# Back_EMF.net
KiCad netlist of a schematic drawn in Altium Designer
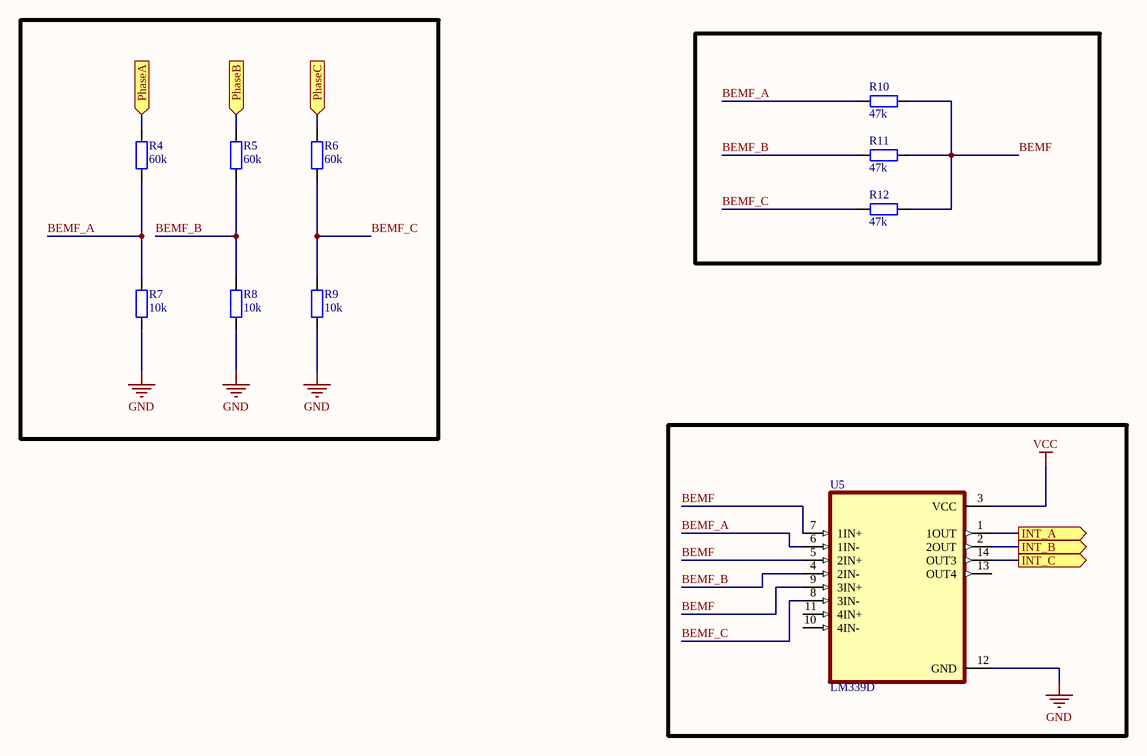
[diagram p0: Back_EMF.SchDoc]

(export (version "E")
  (design (tool "Eeschema 10.0.6"))
  (components
    (comp (ref "R4")
      (value "60k")
      (footprint "tro smd 0603")
      (description "Dán")
      (libsource (lib "Dien Tro") (part "Tro 0603 1% 10k"))
    )
    (comp (ref "R5")
      (value "60k")
      (footprint "tro smd 0603")
      (description "Dán")
      (libsource (lib "Dien Tro") (part "Tro 0603 1% 10k"))
    )
    (comp (ref "R6")
      (value "60k")
      (footprint "tro smd 0603")
      (description "Dán")
      (libsource (lib "Dien Tro") (part "Tro 0603 1% 10k"))
    )
    (comp (ref "R7")
      (value "10k")
      (footprint "tro smd 0603")
      (description "Dán")
      (libsource (lib "Dien Tro") (part "Tro 0603 1% 10k"))
    )
    (comp (ref "R8")
      (value "10k")
      (footprint "tro smd 0603")
      (description "Dán")
      (libsource (lib "Dien Tro") (part "Tro 0603 1% 10k"))
    )
    (comp (ref "R9")
      (value "10k")
      (footprint "tro smd 0603")
      (description "Dán")
      (libsource (lib "Dien Tro") (part "Tro 0603 1% 10k"))
    )
    (comp (ref "R10")
      (value "47k")
      (footprint "tro smd 0603")
      (description "Dán")
      (libsource (lib "Dien Tro") (part "Tro 0603 5% 47k"))
    )
    (comp (ref "R11")
      (value "47k")
      (footprint "tro smd 0603")
      (description "Dán")
      (libsource (lib "Dien Tro") (part "Tro 0603 5% 47k"))
    )
    (comp (ref "R12")
      (value "47k")
      (footprint "tro smd 0603")
      (description "Dán")
      (libsource (lib "Dien Tro") (part "Tro 0603 5% 47k"))
    )
    (comp (ref "U5")
      (value "LM339D")
      (footprint "SOIC127P600X175-14N")
      (libsource (lib "LM339D") (part "LM339D"))
    )
  )
  (nets
    (net (code "1") (name "/BEMF") (class "Default")
      (node (ref "R10") (pin "2") (pinfunction "2_2") (pintype "passive"))
      (node (ref "R11") (pin "2") (pinfunction "2_2") (pintype "passive"))
      (node (ref "R12") (pin "2") (pinfunction "2_2") (pintype "passive"))
      (node (ref "U5") (pin "5") (pinfunction "2IN+_5") (pintype "input"))
      (node (ref "U5") (pin "7") (pinfunction "1IN+_7") (pintype "input"))
      (node (ref "U5") (pin "9") (pinfunction "3IN+_9") (pintype "input"))
    )
    (net (code "2") (name "/BEMF_A") (class "Default")
      (node (ref "R10") (pin "1") (pinfunction "1_1") (pintype "passive"))
      (node (ref "R4") (pin "1") (pinfunction "1_1") (pintype "passive"))
      (node (ref "R7") (pin "2") (pinfunction "2_2") (pintype "passive"))
      (node (ref "U5") (pin "6") (pinfunction "1IN-_6") (pintype "input"))
    )
    (net (code "3") (name "/BEMF_B") (class "Default")
      (node (ref "R11") (pin "1") (pinfunction "1_1") (pintype "passive"))
      (node (ref "R5") (pin "1") (pinfunction "1_1") (pintype "passive"))
      (node (ref "R8") (pin "2") (pinfunction "2_2") (pintype "passive"))
      (node (ref "U5") (pin "4") (pinfunction "2IN-_4") (pintype "input"))
    )
    (net (code "4") (name "/BEMF_C") (class "Default")
      (node (ref "R12") (pin "1") (pinfunction "1_1") (pintype "passive"))
      (node (ref "R6") (pin "1") (pinfunction "1_1") (pintype "passive"))
      (node (ref "R9") (pin "2") (pinfunction "2_2") (pintype "passive"))
      (node (ref "U5") (pin "8") (pinfunction "3IN-_8") (pintype "input"))
    )
    (net (code "5") (name "/INT_A") (class "Default")
      (node (ref "U5") (pin "1") (pinfunction "1OUT_1") (pintype "output"))
    )
    (net (code "6") (name "/INT_B") (class "Default")
      (node (ref "U5") (pin "2") (pinfunction "2OUT_2") (pintype "output"))
    )
    (net (code "7") (name "/INT_C") (class "Default")
      (node (ref "U5") (pin "14") (pinfunction "OUT3_14") (pintype "output"))
    )
    (net (code "8") (name "/PhaseA") (class "Default")
      (node (ref "R4") (pin "2") (pinfunction "2_2") (pintype "passive"))
    )
    (net (code "9") (name "/PhaseB") (class "Default")
      (node (ref "R5") (pin "2") (pinfunction "2_2") (pintype "passive"))
    )
    (net (code "10") (name "/PhaseC") (class "Default")
      (node (ref "R6") (pin "2") (pinfunction "2_2") (pintype "passive"))
    )
    (net (code "11") (name "GND") (class "Default")
      (node (ref "R7") (pin "1") (pinfunction "1_1") (pintype "passive"))
      (node (ref "R8") (pin "1") (pinfunction "1_1") (pintype "passive"))
      (node (ref "R9") (pin "1") (pinfunction "1_1") (pintype "passive"))
      (node (ref "U5") (pin "12") (pinfunction "GND_12") (pintype "power_in"))
    )
    (net (code "12") (name "VCC") (class "Default")
      (node (ref "U5") (pin "3") (pinfunction "VCC_3") (pintype "power_in"))
    )
    (net (code "13") (name "unconnected-(U5-4IN+-Pad11)") (class "Default")
      (node (ref "U5") (pin "11") (pinfunction "4IN+_11") (pintype "input"))
    )
    (net (code "14") (name "unconnected-(U5-4IN--Pad10)") (class "Default")
      (node (ref "U5") (pin "10") (pinfunction "4IN-_10") (pintype "input"))
    )
    (net (code "15") (name "unconnected-(U5-OUT4-Pad13)") (class "Default")
      (node (ref "U5") (pin "13") (pinfunction "OUT4_13") (pintype "output"))
    )
  )
)
